# CADDX.net
KiCad netlist of a schematic drawn in Altium Designer
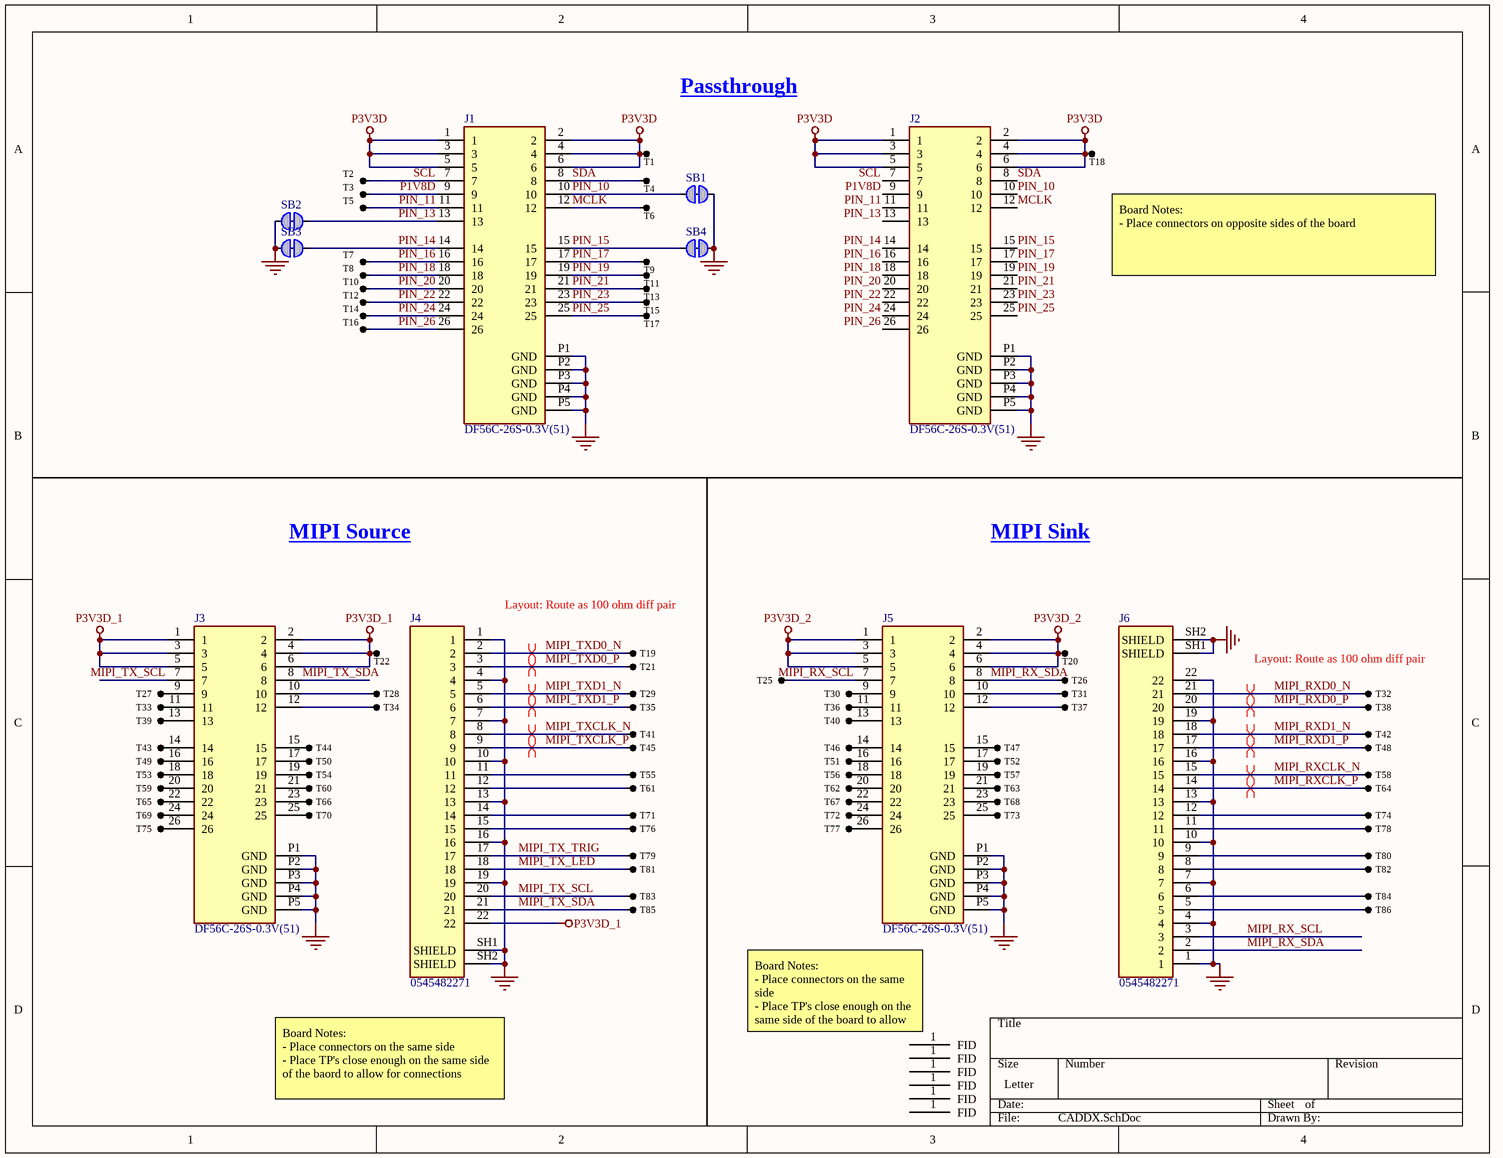
[diagram p0: CADDX.SchDoc]

(export (version "E")
  (design (tool "Eeschema 10.0.6"))
  (components
    (comp (ref "FID1") (value "FID") (footprint "FID_040") (libsource (lib "AiC RVP Adapter") (part "FID")))
    (comp (ref "FID2") (value "FID") (footprint "FID_040") (libsource (lib "AiC RVP Adapter") (part "FID")))
    (comp (ref "FID3") (value "FID") (footprint "FID_040") (libsource (lib "AiC RVP Adapter") (part "FID")))
    (comp (ref "FID4") (value "FID") (footprint "FID_040") (libsource (lib "AiC RVP Adapter") (part "FID")))
    (comp (ref "FID5") (value "FID") (footprint "FID_040") (libsource (lib "AiC RVP Adapter") (part "FID")))
    (comp (ref "FID6") (value "FID") (footprint "FID_040") (libsource (lib "AiC RVP Adapter") (part "FID")))
    (comp (ref "J1")
      (value "DF56C-26S-0.3V(51)")
      (footprint "HRS_DF56C-26S-0.3V(51)")
      (description "0.3mm Pitch, Vertical Mating, Board-to-Fine Coaxial Cable, -35 ℃ to 85 ℃, RoHS")
      (fields (field (name "MANUFACTURER") "Hirose"))
      (libsource (lib "CADDX_passthrough") (part "DF56C-26S-0.3V(51)"))
    )
    (comp (ref "J2")
      (value "DF56C-26S-0.3V(51)")
      (footprint "HRS_DF56C-26S-0.3V(51)")
      (description "0.3mm Pitch, Vertical Mating, Board-to-Fine Coaxial Cable, -35 ℃ to 85 ℃, RoHS")
      (fields (field (name "MANUFACTURER") "Hirose"))
      (libsource (lib "CADDX_passthrough") (part "DF56C-26S-0.3V(51)"))
    )
    (comp (ref "J3")
      (value "DF56C-26S-0.3V(51)")
      (footprint "HRS_DF56C-26S-0.3V(51)")
      (description "0.3mm Pitch, Vertical Mating, Board-to-Fine Coaxial Cable, -35 ℃ to 85 ℃, RoHS")
      (fields (field (name "MANUFACTURER") "Hirose"))
      (libsource (lib "CADDX_passthrough") (part "DF56C-26S-0.3V(51)"))
    )
    (comp (ref "J4")
      (value "0545482271")
      (footprint "MOLEX_54548-2271")
      (description "CONN FFC BOTTOM 22POS 0.50MM R/A")
      (fields (field (name "MANUFACTURER") "Molex"))
      (libsource (lib "") (part "54548-2271_1"))
    )
    (comp (ref "J5")
      (value "DF56C-26S-0.3V(51)")
      (footprint "HRS_DF56C-26S-0.3V(51)")
      (description "0.3mm Pitch, Vertical Mating, Board-to-Fine Coaxial Cable, -35 ℃ to 85 ℃, RoHS")
      (fields (field (name "MANUFACTURER") "Hirose"))
      (libsource (lib "CADDX_passthrough") (part "DF56C-26S-0.3V(51)"))
    )
    (comp (ref "J6")
      (value "0545482271")
      (footprint "MOLEX_54548-2271")
      (description "CONN FFC BOTTOM 22POS 0.50MM R/A")
      (fields (field (name "MANUFACTURER") "Molex"))
      (libsource (lib "CADDX_passthrough") (part "54548-2271"))
    )
    (comp (ref "SB1")
      (value "Solderbridge")
      (footprint "Solderbridge_Shorted")
      (description "Shorted Solderbridge")
      (fields
        (field (name "PART NUMBER") "Solderbridge Shorted")
        (field (name "PUBLISHER") "Nordic Semiconductor")
      )
      (libsource (lib "Tiger_Ti180") (part "Solderbridge Shorted"))
    )
    (comp (ref "SB2")
      (value "Solderbridge")
      (footprint "Solderbridge_Shorted")
      (description "Shorted Solderbridge")
      (fields
        (field (name "PART NUMBER") "Solderbridge Shorted")
        (field (name "PUBLISHER") "Nordic Semiconductor")
      )
      (libsource (lib "Tiger_Ti180") (part "Solderbridge Shorted"))
    )
    (comp (ref "SB3")
      (value "Solderbridge")
      (footprint "Solderbridge_Shorted")
      (description "Shorted Solderbridge")
      (fields
        (field (name "PART NUMBER") "Solderbridge Shorted")
        (field (name "PUBLISHER") "Nordic Semiconductor")
      )
      (libsource (lib "Tiger_Ti180") (part "Solderbridge Shorted"))
    )
    (comp (ref "SB4")
      (value "Solderbridge")
      (footprint "Solderbridge_Shorted")
      (description "Shorted Solderbridge")
      (fields
        (field (name "PART NUMBER") "Solderbridge Shorted")
        (field (name "PUBLISHER") "Nordic Semiconductor")
      )
      (libsource (lib "Tiger_Ti180") (part "Solderbridge Shorted"))
    )
    (comp (ref "T1")
      (value "~")
      (footprint "TP 1mm")
      (description "test point")
      (libsource (lib "Tiger_Ti180") (part "TP_S"))
    )
    (comp (ref "T2")
      (value "~")
      (footprint "TP 1mm")
      (description "test point")
      (libsource (lib "Tiger_Ti180") (part "TP_S"))
    )
    (comp (ref "T3")
      (value "~")
      (footprint "TP 1mm")
      (description "test point")
      (libsource (lib "Tiger_Ti180") (part "TP_S"))
    )
    (comp (ref "T4")
      (value "~")
      (footprint "TP 1mm")
      (description "test point")
      (libsource (lib "Tiger_Ti180") (part "TP_S"))
    )
    (comp (ref "T5")
      (value "~")
      (footprint "TP 1mm")
      (description "test point")
      (libsource (lib "Tiger_Ti180") (part "TP_S"))
    )
    (comp (ref "T6")
      (value "~")
      (footprint "TP 1mm")
      (description "test point")
      (libsource (lib "Tiger_Ti180") (part "TP_S"))
    )
    (comp (ref "T7")
      (value "~")
      (footprint "TP 1mm")
      (description "test point")
      (libsource (lib "Tiger_Ti180") (part "TP_S"))
    )
    (comp (ref "T8")
      (value "~")
      (footprint "TP 1mm")
      (description "test point")
      (libsource (lib "Tiger_Ti180") (part "TP_S"))
    )
    (comp (ref "T9")
      (value "~")
      (footprint "TP 1mm")
      (description "test point")
      (libsource (lib "Tiger_Ti180") (part "TP_S"))
    )
    (comp (ref "T10")
      (value "~")
      (footprint "TP 1mm")
      (description "test point")
      (libsource (lib "Tiger_Ti180") (part "TP_S"))
    )
    (comp (ref "T11")
      (value "~")
      (footprint "TP 1mm")
      (description "test point")
      (libsource (lib "Tiger_Ti180") (part "TP_S"))
    )
    (comp (ref "T12")
      (value "~")
      (footprint "TP 1mm")
      (description "test point")
      (libsource (lib "Tiger_Ti180") (part "TP_S"))
    )
    (comp (ref "T13")
      (value "~")
      (footprint "TP 1mm")
      (description "test point")
      (libsource (lib "Tiger_Ti180") (part "TP_S"))
    )
    (comp (ref "T14")
      (value "~")
      (footprint "TP 1mm")
      (description "test point")
      (libsource (lib "Tiger_Ti180") (part "TP_S"))
    )
    (comp (ref "T15")
      (value "~")
      (footprint "TP 1mm")
      (description "test point")
      (libsource (lib "Tiger_Ti180") (part "TP_S"))
    )
    (comp (ref "T16")
      (value "~")
      (footprint "TP 1mm")
      (description "test point")
      (libsource (lib "Tiger_Ti180") (part "TP_S"))
    )
    (comp (ref "T17")
      (value "~")
      (footprint "TP 1mm")
      (description "test point")
      (libsource (lib "Tiger_Ti180") (part "TP_S"))
    )
    (comp (ref "T18")
      (value "~")
      (footprint "TP 1mm")
      (description "test point")
      (libsource (lib "Tiger_Ti180") (part "TP_S"))
    )
    (comp (ref "T19")
      (value "~")
      (footprint "TP 1mm")
      (description "test point")
      (libsource (lib "Tiger_Ti180") (part "TP_S"))
    )
    (comp (ref "T20")
      (value "~")
      (footprint "TP 1mm")
      (description "test point")
      (libsource (lib "Tiger_Ti180") (part "TP_S"))
    )
    (comp (ref "T21")
      (value "~")
      (footprint "TP 1mm")
      (description "test point")
      (libsource (lib "Tiger_Ti180") (part "TP_S"))
    )
    (comp (ref "T22")
      (value "~")
      (footprint "TP 1mm")
      (description "test point")
      (libsource (lib "Tiger_Ti180") (part "TP_S"))
    )
    (comp (ref "T25")
      (value "~")
      (footprint "TP 1mm")
      (description "test point")
      (libsource (lib "Tiger_Ti180") (part "TP_S"))
    )
    (comp (ref "T26")
      (value "~")
      (footprint "TP 1mm")
      (description "test point")
      (libsource (lib "Tiger_Ti180") (part "TP_S"))
    )
    (comp (ref "T27")
      (value "~")
      (footprint "TP 1mm")
      (description "test point")
      (libsource (lib "Tiger_Ti180") (part "TP_S"))
    )
    (comp (ref "T28")
      (value "~")
      (footprint "TP 1mm")
      (description "test point")
      (libsource (lib "Tiger_Ti180") (part "TP_S"))
    )
    (comp (ref "T29")
      (value "~")
      (footprint "TP 1mm")
      (description "test point")
      (libsource (lib "Tiger_Ti180") (part "TP_S"))
    )
    (comp (ref "T30")
      (value "~")
      (footprint "TP 1mm")
      (description "test point")
      (libsource (lib "Tiger_Ti180") (part "TP_S"))
    )
    (comp (ref "T31")
      (value "~")
      (footprint "TP 1mm")
      (description "test point")
      (libsource (lib "Tiger_Ti180") (part "TP_S"))
    )
    (comp (ref "T32")
      (value "~")
      (footprint "TP 1mm")
      (description "test point")
      (libsource (lib "Tiger_Ti180") (part "TP_S"))
    )
    (comp (ref "T33")
      (value "~")
      (footprint "TP 1mm")
      (description "test point")
      (libsource (lib "Tiger_Ti180") (part "TP_S"))
    )
    (comp (ref "T34")
      (value "~")
      (footprint "TP 1mm")
      (description "test point")
      (libsource (lib "Tiger_Ti180") (part "TP_S"))
    )
    (comp (ref "T35")
      (value "~")
      (footprint "TP 1mm")
      (description "test point")
      (libsource (lib "Tiger_Ti180") (part "TP_S"))
    )
    (comp (ref "T36")
      (value "~")
      (footprint "TP 1mm")
      (description "test point")
      (libsource (lib "Tiger_Ti180") (part "TP_S"))
    )
    (comp (ref "T37")
      (value "~")
      (footprint "TP 1mm")
      (description "test point")
      (libsource (lib "Tiger_Ti180") (part "TP_S"))
    )
    (comp (ref "T38")
      (value "~")
      (footprint "TP 1mm")
      (description "test point")
      (libsource (lib "Tiger_Ti180") (part "TP_S"))
    )
    (comp (ref "T39")
      (value "~")
      (footprint "TP 1mm")
      (description "test point")
      (libsource (lib "Tiger_Ti180") (part "TP_S"))
    )
    (comp (ref "T40")
      (value "~")
      (footprint "TP 1mm")
      (description "test point")
      (libsource (lib "Tiger_Ti180") (part "TP_S"))
    )
    (comp (ref "T41")
      (value "~")
      (footprint "TP 1mm")
      (description "test point")
      (libsource (lib "Tiger_Ti180") (part "TP_S"))
    )
    (comp (ref "T42")
      (value "~")
      (footprint "TP 1mm")
      (description "test point")
      (libsource (lib "Tiger_Ti180") (part "TP_S"))
    )
    (comp (ref "T43")
      (value "~")
      (footprint "TP 1mm")
      (description "test point")
      (libsource (lib "Tiger_Ti180") (part "TP_S"))
    )
    (comp (ref "T44")
      (value "~")
      (footprint "TP 1mm")
      (description "test point")
      (libsource (lib "Tiger_Ti180") (part "TP_S"))
    )
    (comp (ref "T45")
      (value "~")
      (footprint "TP 1mm")
      (description "test point")
      (libsource (lib "Tiger_Ti180") (part "TP_S"))
    )
    (comp (ref "T46")
      (value "~")
      (footprint "TP 1mm")
      (description "test point")
      (libsource (lib "Tiger_Ti180") (part "TP_S"))
    )
    (comp (ref "T47")
      (value "~")
      (footprint "TP 1mm")
      (description "test point")
      (libsource (lib "Tiger_Ti180") (part "TP_S"))
    )
    (comp (ref "T48")
      (value "~")
      (footprint "TP 1mm")
      (description "test point")
      (libsource (lib "Tiger_Ti180") (part "TP_S"))
    )
    (comp (ref "T49")
      (value "~")
      (footprint "TP 1mm")
      (description "test point")
      (libsource (lib "Tiger_Ti180") (part "TP_S"))
    )
    (comp (ref "T50")
      (value "~")
      (footprint "TP 1mm")
      (description "test point")
      (libsource (lib "Tiger_Ti180") (part "TP_S"))
    )
    (comp (ref "T51")
      (value "~")
      (footprint "TP 1mm")
      (description "test point")
      (libsource (lib "Tiger_Ti180") (part "TP_S"))
    )
    (comp (ref "T52")
      (value "~")
      (footprint "TP 1mm")
      (description "test point")
      (libsource (lib "Tiger_Ti180") (part "TP_S"))
    )
    (comp (ref "T53")
      (value "~")
      (footprint "TP 1mm")
      (description "test point")
      (libsource (lib "Tiger_Ti180") (part "TP_S"))
    )
    (comp (ref "T54")
      (value "~")
      (footprint "TP 1mm")
      (description "test point")
      (libsource (lib "Tiger_Ti180") (part "TP_S"))
    )
    (comp (ref "T55")
      (value "~")
      (footprint "TP 1mm")
      (description "test point")
      (libsource (lib "Tiger_Ti180") (part "TP_S"))
    )
    (comp (ref "T56")
      (value "~")
      (footprint "TP 1mm")
      (description "test point")
      (libsource (lib "Tiger_Ti180") (part "TP_S"))
    )
    (comp (ref "T57")
      (value "~")
      (footprint "TP 1mm")
      (description "test point")
      (libsource (lib "Tiger_Ti180") (part "TP_S"))
    )
    (comp (ref "T58")
      (value "~")
      (footprint "TP 1mm")
      (description "test point")
      (libsource (lib "Tiger_Ti180") (part "TP_S"))
    )
    (comp (ref "T59")
      (value "~")
      (footprint "TP 1mm")
      (description "test point")
      (libsource (lib "Tiger_Ti180") (part "TP_S"))
    )
    (comp (ref "T60")
      (value "~")
      (footprint "TP 1mm")
      (description "test point")
      (libsource (lib "Tiger_Ti180") (part "TP_S"))
    )
    (comp (ref "T61")
      (value "~")
      (footprint "TP 1mm")
      (description "test point")
      (libsource (lib "Tiger_Ti180") (part "TP_S"))
    )
    (comp (ref "T62")
      (value "~")
      (footprint "TP 1mm")
      (description "test point")
      (libsource (lib "Tiger_Ti180") (part "TP_S"))
    )
    (comp (ref "T63")
      (value "~")
      (footprint "TP 1mm")
      (description "test point")
      (libsource (lib "Tiger_Ti180") (part "TP_S"))
    )
    (comp (ref "T64")
      (value "~")
      (footprint "TP 1mm")
      (description "test point")
      (libsource (lib "Tiger_Ti180") (part "TP_S"))
    )
    (comp (ref "T65")
      (value "~")
      (footprint "TP 1mm")
      (description "test point")
      (libsource (lib "Tiger_Ti180") (part "TP_S"))
    )
    (comp (ref "T66")
      (value "~")
      (footprint "TP 1mm")
      (description "test point")
      (libsource (lib "Tiger_Ti180") (part "TP_S"))
    )
    (comp (ref "T67")
      (value "~")
      (footprint "TP 1mm")
      (description "test point")
      (libsource (lib "Tiger_Ti180") (part "TP_S"))
    )
    (comp (ref "T68")
      (value "~")
      (footprint "TP 1mm")
      (description "test point")
      (libsource (lib "Tiger_Ti180") (part "TP_S"))
    )
    (comp (ref "T69")
      (value "~")
      (footprint "TP 1mm")
      (description "test point")
      (libsource (lib "Tiger_Ti180") (part "TP_S"))
    )
    (comp (ref "T70")
      (value "~")
      (footprint "TP 1mm")
      (description "test point")
      (libsource (lib "Tiger_Ti180") (part "TP_S"))
    )
    (comp (ref "T71")
      (value "~")
      (footprint "TP 1mm")
      (description "test point")
      (libsource (lib "Tiger_Ti180") (part "TP_S"))
    )
    (comp (ref "T72")
      (value "~")
      (footprint "TP 1mm")
      (description "test point")
      (libsource (lib "Tiger_Ti180") (part "TP_S"))
    )
    (comp (ref "T73")
      (value "~")
      (footprint "TP 1mm")
      (description "test point")
      (libsource (lib "Tiger_Ti180") (part "TP_S"))
    )
    (comp (ref "T74")
      (value "~")
      (footprint "TP 1mm")
      (description "test point")
      (libsource (lib "Tiger_Ti180") (part "TP_S"))
    )
    (comp (ref "T75")
      (value "~")
      (footprint "TP 1mm")
      (description "test point")
      (libsource (lib "Tiger_Ti180") (part "TP_S"))
    )
    (comp (ref "T76")
      (value "~")
      (footprint "TP 1mm")
      (description "test point")
      (libsource (lib "Tiger_Ti180") (part "TP_S"))
    )
    (comp (ref "T77")
      (value "~")
      (footprint "TP 1mm")
      (description "test point")
      (libsource (lib "Tiger_Ti180") (part "TP_S"))
    )
    (comp (ref "T78")
      (value "~")
      (footprint "TP 1mm")
      (description "test point")
      (libsource (lib "Tiger_Ti180") (part "TP_S"))
    )
    (comp (ref "T79")
      (value "~")
      (footprint "TP 1mm")
      (description "test point")
      (libsource (lib "Tiger_Ti180") (part "TP_S"))
    )
    (comp (ref "T80")
      (value "~")
      (footprint "TP 1mm")
      (description "test point")
      (libsource (lib "Tiger_Ti180") (part "TP_S"))
    )
    (comp (ref "T81")
      (value "~")
      (footprint "TP 1mm")
      (description "test point")
      (libsource (lib "Tiger_Ti180") (part "TP_S"))
    )
    (comp (ref "T82")
      (value "~")
      (footprint "TP 1mm")
      (description "test point")
      (libsource (lib "Tiger_Ti180") (part "TP_S"))
    )
    (comp (ref "T83")
      (value "~")
      (footprint "TP 1mm")
      (description "test point")
      (libsource (lib "Tiger_Ti180") (part "TP_S"))
    )
    (comp (ref "T84")
      (value "~")
      (footprint "TP 1mm")
      (description "test point")
      (libsource (lib "Tiger_Ti180") (part "TP_S"))
    )
    (comp (ref "T85")
      (value "~")
      (footprint "TP 1mm")
      (description "test point")
      (libsource (lib "Tiger_Ti180") (part "TP_S"))
    )
    (comp (ref "T86")
      (value "~")
      (footprint "TP 1mm")
      (description "test point")
      (libsource (lib "Tiger_Ti180") (part "TP_S"))
    )
  )
  (nets
    (net (code "1") (name "/MCLK") (class "Default")
      (node (ref "J1") (pin "12") (pinfunction "12_12") (pintype "passive"))
      (node (ref "J2") (pin "12") (pinfunction "12_12") (pintype "passive"))
      (node (ref "T6") (pin "1") (pintype "passive"))
    )
    (net (code "2") (name "/MIPI_RXCLK_N") (class "Default")
      (node (ref "J6") (pin "15") (pinfunction "15_15") (pintype "passive"))
      (node (ref "T58") (pin "1") (pintype "passive"))
    )
    (net (code "3") (name "/MIPI_RXCLK_P") (class "Default")
      (node (ref "J6") (pin "14") (pinfunction "14_14") (pintype "passive"))
      (node (ref "T64") (pin "1") (pintype "passive"))
    )
    (net (code "4") (name "/MIPI_RXD0_N") (class "Default")
      (node (ref "J6") (pin "21") (pinfunction "21_21") (pintype "passive"))
      (node (ref "T32") (pin "1") (pintype "passive"))
    )
    (net (code "5") (name "/MIPI_RXD0_P") (class "Default")
      (node (ref "J6") (pin "20") (pinfunction "20_20") (pintype "passive"))
      (node (ref "T38") (pin "1") (pintype "passive"))
    )
    (net (code "6") (name "/MIPI_RXD1_N") (class "Default")
      (node (ref "J6") (pin "18") (pinfunction "18_18") (pintype "passive"))
      (node (ref "T42") (pin "1") (pintype "passive"))
    )
    (net (code "7") (name "/MIPI_RXD1_P") (class "Default")
      (node (ref "J6") (pin "17") (pinfunction "17_17") (pintype "passive"))
      (node (ref "T48") (pin "1") (pintype "passive"))
    )
    (net (code "8") (name "/MIPI_RX_SCL") (class "Default")
      (node (ref "J5") (pin "7") (pinfunction "7_7") (pintype "passive"))
      (node (ref "J6") (pin "3") (pinfunction "3_3") (pintype "passive"))
      (node (ref "T25") (pin "1") (pintype "passive"))
    )
    (net (code "9") (name "/MIPI_RX_SDA") (class "Default")
      (node (ref "J5") (pin "8") (pinfunction "8_8") (pintype "passive"))
      (node (ref "J6") (pin "2") (pinfunction "2_2") (pintype "passive"))
      (node (ref "T26") (pin "1") (pintype "passive"))
    )
    (net (code "10") (name "/MIPI_TXCLK_N") (class "Default")
      (node (ref "J4") (pin "8") (pinfunction "8_8") (pintype "passive"))
      (node (ref "T41") (pin "1") (pintype "passive"))
    )
    (net (code "11") (name "/MIPI_TXCLK_P") (class "Default")
      (node (ref "J4") (pin "9") (pinfunction "9_9") (pintype "passive"))
      (node (ref "T45") (pin "1") (pintype "passive"))
    )
    (net (code "12") (name "/MIPI_TXD0_N") (class "Default")
      (node (ref "J4") (pin "2") (pinfunction "2_2") (pintype "passive"))
      (node (ref "T19") (pin "1") (pintype "passive"))
    )
    (net (code "13") (name "/MIPI_TXD0_P") (class "Default")
      (node (ref "J4") (pin "3") (pinfunction "3_3") (pintype "passive"))
      (node (ref "T21") (pin "1") (pintype "passive"))
    )
    (net (code "14") (name "/MIPI_TXD1_N") (class "Default")
      (node (ref "J4") (pin "5") (pinfunction "5_5") (pintype "passive"))
      (node (ref "T29") (pin "1") (pintype "passive"))
    )
    (net (code "15") (name "/MIPI_TXD1_P") (class "Default")
      (node (ref "J4") (pin "6") (pinfunction "6_6") (pintype "passive"))
      (node (ref "T35") (pin "1") (pintype "passive"))
    )
    (net (code "16") (name "/MIPI_TX_LED") (class "Default")
      (node (ref "J4") (pin "18") (pinfunction "18_18") (pintype "passive"))
      (node (ref "T81") (pin "1") (pintype "passive"))
    )
    (net (code "17") (name "/MIPI_TX_SCL") (class "Default")
      (node (ref "J3") (pin "7") (pinfunction "7_7") (pintype "passive"))
      (node (ref "J4") (pin "20") (pinfunction "20_20") (pintype "passive"))
      (node (ref "T83") (pin "1") (pintype "passive"))
    )
    (net (code "18") (name "/MIPI_TX_SDA") (class "Default")
      (node (ref "J3") (pin "8") (pinfunction "8_8") (pintype "passive"))
      (node (ref "J4") (pin "21") (pinfunction "21_21") (pintype "passive"))
      (node (ref "T85") (pin "1") (pintype "passive"))
    )
    (net (code "19") (name "/MIPI_TX_TRIG") (class "Default")
      (node (ref "J4") (pin "17") (pinfunction "17_17") (pintype "passive"))
      (node (ref "T79") (pin "1") (pintype "passive"))
    )
    (net (code "20") (name "/P1V8D") (class "Default")
      (node (ref "J1") (pin "9") (pinfunction "9_9") (pintype "passive"))
      (node (ref "J2") (pin "9") (pinfunction "9_9") (pintype "passive"))
      (node (ref "T3") (pin "1") (pintype "passive"))
    )
    (net (code "21") (name "/PIN_10") (class "Default")
      (node (ref "J1") (pin "10") (pinfunction "10_10") (pintype "passive"))
      (node (ref "J2") (pin "10") (pinfunction "10_10") (pintype "passive"))
      (node (ref "SB1") (pin "2") (pinfunction "1_2") (pintype "passive"))
    )
    (net (code "22") (name "/PIN_11") (class "Default")
      (node (ref "J1") (pin "11") (pinfunction "11_11") (pintype "passive"))
      (node (ref "J2") (pin "11") (pinfunction "11_11") (pintype "passive"))
      (node (ref "T5") (pin "1") (pintype "passive"))
    )
    (net (code "23") (name "/PIN_13") (class "Default")
      (node (ref "J1") (pin "13") (pinfunction "13_13") (pintype "passive"))
      (node (ref "J2") (pin "13") (pinfunction "13_13") (pintype "passive"))
      (node (ref "SB2") (pin "1") (pinfunction "0_1") (pintype "passive"))
    )
    (net (code "24") (name "/PIN_14") (class "Default")
      (node (ref "J1") (pin "14") (pinfunction "14_14") (pintype "passive"))
      (node (ref "J2") (pin "14") (pinfunction "14_14") (pintype "passive"))
      (node (ref "SB3") (pin "1") (pinfunction "0_1") (pintype "passive"))
    )
    (net (code "25") (name "/PIN_15") (class "Default")
      (node (ref "J1") (pin "15") (pinfunction "15_15") (pintype "passive"))
      (node (ref "J2") (pin "15") (pinfunction "15_15") (pintype "passive"))
      (node (ref "SB4") (pin "2") (pinfunction "1_2") (pintype "passive"))
    )
    (net (code "26") (name "/PIN_16") (class "Default")
      (node (ref "J1") (pin "16") (pinfunction "16_16") (pintype "passive"))
      (node (ref "J2") (pin "16") (pinfunction "16_16") (pintype "passive"))
      (node (ref "T7") (pin "1") (pintype "passive"))
    )
    (net (code "27") (name "/PIN_17") (class "Default")
      (node (ref "J1") (pin "17") (pinfunction "17_17") (pintype "passive"))
      (node (ref "J2") (pin "17") (pinfunction "17_17") (pintype "passive"))
      (node (ref "T9") (pin "1") (pintype "passive"))
    )
    (net (code "28") (name "/PIN_18") (class "Default")
      (node (ref "J1") (pin "18") (pinfunction "18_18") (pintype "passive"))
      (node (ref "J2") (pin "18") (pinfunction "18_18") (pintype "passive"))
      (node (ref "T8") (pin "1") (pintype "passive"))
    )
    (net (code "29") (name "/PIN_19") (class "Default")
      (node (ref "J1") (pin "19") (pinfunction "19_19") (pintype "passive"))
      (node (ref "J2") (pin "19") (pinfunction "19_19") (pintype "passive"))
      (node (ref "T11") (pin "1") (pintype "passive"))
    )
    (net (code "30") (name "/PIN_20") (class "Default")
      (node (ref "J1") (pin "20") (pinfunction "20_20") (pintype "passive"))
      (node (ref "J2") (pin "20") (pinfunction "20_20") (pintype "passive"))
      (node (ref "T10") (pin "1") (pintype "passive"))
    )
    (net (code "31") (name "/PIN_21") (class "Default")
      (node (ref "J1") (pin "21") (pinfunction "21_21") (pintype "passive"))
      (node (ref "J2") (pin "21") (pinfunction "21_21") (pintype "passive"))
      (node (ref "T13") (pin "1") (pintype "passive"))
    )
    (net (code "32") (name "/PIN_22") (class "Default")
      (node (ref "J1") (pin "22") (pinfunction "22_22") (pintype "passive"))
      (node (ref "J2") (pin "22") (pinfunction "22_22") (pintype "passive"))
      (node (ref "T12") (pin "1") (pintype "passive"))
    )
    (net (code "33") (name "/PIN_23") (class "Default")
      (node (ref "J1") (pin "23") (pinfunction "23_23") (pintype "passive"))
      (node (ref "J2") (pin "23") (pinfunction "23_23") (pintype "passive"))
      (node (ref "T15") (pin "1") (pintype "passive"))
    )
    (net (code "34") (name "/PIN_24") (class "Default")
      (node (ref "J1") (pin "24") (pinfunction "24_24") (pintype "passive"))
      (node (ref "J2") (pin "24") (pinfunction "24_24") (pintype "passive"))
      (node (ref "T14") (pin "1") (pintype "passive"))
    )
    (net (code "35") (name "/PIN_25") (class "Default")
      (node (ref "J1") (pin "25") (pinfunction "25_25") (pintype "passive"))
      (node (ref "J2") (pin "25") (pinfunction "25_25") (pintype "passive"))
      (node (ref "T17") (pin "1") (pintype "passive"))
    )
    (net (code "36") (name "/PIN_26") (class "Default")
      (node (ref "J1") (pin "26") (pinfunction "26_26") (pintype "passive"))
      (node (ref "J2") (pin "26") (pinfunction "26_26") (pintype "passive"))
      (node (ref "T16") (pin "1") (pintype "passive"))
    )
    (net (code "37") (name "/SCL") (class "Default")
      (node (ref "J1") (pin "7") (pinfunction "7_7") (pintype "passive"))
      (node (ref "J2") (pin "7") (pinfunction "7_7") (pintype "passive"))
      (node (ref "T2") (pin "1") (pintype "passive"))
    )
    (net (code "38") (name "/SDA") (class "Default")
      (node (ref "J1") (pin "8") (pinfunction "8_8") (pintype "passive"))
      (node (ref "J2") (pin "8") (pinfunction "8_8") (pintype "passive"))
      (node (ref "T4") (pin "1") (pintype "passive"))
    )
    (net (code "39") (name "GND") (class "Default")
      (node (ref "J1") (pin "P1") (pinfunction "GND_P1") (pintype "power_in"))
      (node (ref "J1") (pin "P2") (pinfunction "GND_P2") (pintype "power_in"))
      (node (ref "J1") (pin "P3") (pinfunction "GND_P3") (pintype "power_in"))
      (node (ref "J1") (pin "P4") (pinfunction "GND_P4") (pintype "power_in"))
      (node (ref "J1") (pin "P5") (pinfunction "GND_P5") (pintype "power_in"))
      (node (ref "J2") (pin "P1") (pinfunction "GND_P1") (pintype "power_in"))
      (node (ref "J2") (pin "P2") (pinfunction "GND_P2") (pintype "power_in"))
      (node (ref "J2") (pin "P3") (pinfunction "GND_P3") (pintype "power_in"))
      (node (ref "J2") (pin "P4") (pinfunction "GND_P4") (pintype "power_in"))
      (node (ref "J2") (pin "P5") (pinfunction "GND_P5") (pintype "power_in"))
      (node (ref "J3") (pin "P1") (pinfunction "GND_P1") (pintype "power_in"))
      (node (ref "J3") (pin "P2") (pinfunction "GND_P2") (pintype "power_in"))
      (node (ref "J3") (pin "P3") (pinfunction "GND_P3") (pintype "power_in"))
      (node (ref "J3") (pin "P4") (pinfunction "GND_P4") (pintype "power_in"))
      (node (ref "J3") (pin "P5") (pinfunction "GND_P5") (pintype "power_in"))
      (node (ref "J4") (pin "1") (pinfunction "1_1") (pintype "passive"))
      (node (ref "J4") (pin "10") (pinfunction "10_10") (pintype "passive"))
      (node (ref "J4") (pin "13") (pinfunction "13_13") (pintype "passive"))
      (node (ref "J4") (pin "16") (pinfunction "16_16") (pintype "passive"))
      (node (ref "J4") (pin "19") (pinfunction "19_19") (pintype "passive"))
      (node (ref "J4") (pin "4") (pinfunction "4_4") (pintype "passive"))
      (node (ref "J4") (pin "7") (pinfunction "7_7") (pintype "passive"))
      (node (ref "J4") (pin "SH1") (pinfunction "SHIELD_SH1") (pintype "passive"))
      (node (ref "J4") (pin "SH2") (pinfunction "SHIELD_SH2") (pintype "passive"))
      (node (ref "J5") (pin "P1") (pinfunction "GND_P1") (pintype "power_in"))
      (node (ref "J5") (pin "P2") (pinfunction "GND_P2") (pintype "power_in"))
      (node (ref "J5") (pin "P3") (pinfunction "GND_P3") (pintype "power_in"))
      (node (ref "J5") (pin "P4") (pinfunction "GND_P4") (pintype "power_in"))
      (node (ref "J5") (pin "P5") (pinfunction "GND_P5") (pintype "power_in"))
      (node (ref "J6") (pin "1") (pinfunction "1_1") (pintype "passive"))
      (node (ref "J6") (pin "10") (pinfunction "10_10") (pintype "passive"))
      (node (ref "J6") (pin "13") (pinfunction "13_13") (pintype "passive"))
      (node (ref "J6") (pin "16") (pinfunction "16_16") (pintype "passive"))
      (node (ref "J6") (pin "19") (pinfunction "19_19") (pintype "passive"))
      (node (ref "J6") (pin "22") (pinfunction "22_22") (pintype "passive"))
      (node (ref "J6") (pin "4") (pinfunction "4_4") (pintype "passive"))
      (node (ref "J6") (pin "7") (pinfunction "7_7") (pintype "passive"))
      (node (ref "J6") (pin "SH1") (pinfunction "SHIELD_SH1") (pintype "passive"))
      (node (ref "J6") (pin "SH2") (pinfunction "SHIELD_SH2") (pintype "passive"))
      (node (ref "SB1") (pin "1") (pinfunction "0_1") (pintype "passive"))
      (node (ref "SB2") (pin "2") (pinfunction "1_2") (pintype "passive"))
      (node (ref "SB3") (pin "2") (pinfunction "1_2") (pintype "passive"))
      (node (ref "SB4") (pin "1") (pinfunction "0_1") (pintype "passive"))
    )
    (net (code "40") (name "Net-(J3-Pad9)") (class "Default")
      (node (ref "J3") (pin "9") (pinfunction "9_9") (pintype "passive"))
      (node (ref "T27") (pin "1") (pintype "passive"))
    )
    (net (code "41") (name "Net-(J3-Pad10)") (class "Default")
      (node (ref "J3") (pin "10") (pinfunction "10_10") (pintype "passive"))
      (node (ref "T28") (pin "1") (pintype "passive"))
    )
    (net (code "42") (name "Net-(J3-Pad11)") (class "Default")
      (node (ref "J3") (pin "11") (pinfunction "11_11") (pintype "passive"))
      (node (ref "T33") (pin "1") (pintype "passive"))
    )
    (net (code "43") (name "Net-(J3-Pad12)") (class "Default")
      (node (ref "J3") (pin "12") (pinfunction "12_12") (pintype "passive"))
      (node (ref "T34") (pin "1") (pintype "passive"))
    )
    (net (code "44") (name "Net-(J3-Pad13)") (class "Default")
      (node (ref "J3") (pin "13") (pinfunction "13_13") (pintype "passive"))
      (node (ref "T39") (pin "1") (pintype "passive"))
    )
    (net (code "45") (name "Net-(J3-Pad14)") (class "Default")
      (node (ref "J3") (pin "14") (pinfunction "14_14") (pintype "passive"))
      (node (ref "T43") (pin "1") (pintype "passive"))
    )
    (net (code "46") (name "Net-(J3-Pad15)") (class "Default")
      (node (ref "J3") (pin "15") (pinfunction "15_15") (pintype "passive"))
      (node (ref "T44") (pin "1") (pintype "passive"))
    )
    (net (code "47") (name "Net-(J3-Pad16)") (class "Default")
      (node (ref "J3") (pin "16") (pinfunction "16_16") (pintype "passive"))
      (node (ref "T49") (pin "1") (pintype "passive"))
    )
    (net (code "48") (name "Net-(J3-Pad17)") (class "Default")
      (node (ref "J3") (pin "17") (pinfunction "17_17") (pintype "passive"))
      (node (ref "T50") (pin "1") (pintype "passive"))
    )
    (net (code "49") (name "Net-(J3-Pad18)") (class "Default")
      (node (ref "J3") (pin "18") (pinfunction "18_18") (pintype "passive"))
      (node (ref "T53") (pin "1") (pintype "passive"))
    )
    (net (code "50") (name "Net-(J3-Pad19)") (class "Default")
      (node (ref "J3") (pin "19") (pinfunction "19_19") (pintype "passive"))
      (node (ref "T54") (pin "1") (pintype "passive"))
    )
    (net (code "51") (name "Net-(J3-Pad20)") (class "Default")
      (node (ref "J3") (pin "20") (pinfunction "20_20") (pintype "passive"))
      (node (ref "T59") (pin "1") (pintype "passive"))
    )
    (net (code "52") (name "Net-(J3-Pad21)") (class "Default")
      (node (ref "J3") (pin "21") (pinfunction "21_21") (pintype "passive"))
      (node (ref "T60") (pin "1") (pintype "passive"))
    )
    (net (code "53") (name "Net-(J3-Pad22)") (class "Default")
      (node (ref "J3") (pin "22") (pinfunction "22_22") (pintype "passive"))
      (node (ref "T65") (pin "1") (pintype "passive"))
    )
    (net (code "54") (name "Net-(J3-Pad23)") (class "Default")
      (node (ref "J3") (pin "23") (pinfunction "23_23") (pintype "passive"))
      (node (ref "T66") (pin "1") (pintype "passive"))
    )
    (net (code "55") (name "Net-(J3-Pad24)") (class "Default")
      (node (ref "J3") (pin "24") (pinfunction "24_24") (pintype "passive"))
      (node (ref "T69") (pin "1") (pintype "passive"))
    )
    (net (code "56") (name "Net-(J3-Pad25)") (class "Default")
      (node (ref "J3") (pin "25") (pinfunction "25_25") (pintype "passive"))
      (node (ref "T70") (pin "1") (pintype "passive"))
    )
    (net (code "57") (name "Net-(J3-Pad26)") (class "Default")
      (node (ref "J3") (pin "26") (pinfunction "26_26") (pintype "passive"))
      (node (ref "T75") (pin "1") (pintype "passive"))
    )
    (net (code "58") (name "Net-(J4-Pad11)") (class "Default")
      (node (ref "J4") (pin "11") (pinfunction "11_11") (pintype "passive"))
      (node (ref "T55") (pin "1") (pintype "passive"))
    )
    (net (code "59") (name "Net-(J4-Pad12)") (class "Default")
      (node (ref "J4") (pin "12") (pinfunction "12_12") (pintype "passive"))
      (node (ref "T61") (pin "1") (pintype "passive"))
    )
    (net (code "60") (name "Net-(J4-Pad14)") (class "Default")
      (node (ref "J4") (pin "14") (pinfunction "14_14") (pintype "passive"))
      (node (ref "T71") (pin "1") (pintype "passive"))
    )
    (net (code "61") (name "Net-(J4-Pad15)") (class "Default")
      (node (ref "J4") (pin "15") (pinfunction "15_15") (pintype "passive"))
      (node (ref "T76") (pin "1") (pintype "passive"))
    )
    (net (code "62") (name "Net-(J5-Pad9)") (class "Default")
      (node (ref "J5") (pin "9") (pinfunction "9_9") (pintype "passive"))
      (node (ref "T30") (pin "1") (pintype "passive"))
    )
    (net (code "63") (name "Net-(J5-Pad10)") (class "Default")
      (node (ref "J5") (pin "10") (pinfunction "10_10") (pintype "passive"))
      (node (ref "T31") (pin "1") (pintype "passive"))
    )
    (net (code "64") (name "Net-(J5-Pad11)") (class "Default")
      (node (ref "J5") (pin "11") (pinfunction "11_11") (pintype "passive"))
      (node (ref "T36") (pin "1") (pintype "passive"))
    )
    (net (code "65") (name "Net-(J5-Pad12)") (class "Default")
      (node (ref "J5") (pin "12") (pinfunction "12_12") (pintype "passive"))
      (node (ref "T37") (pin "1") (pintype "passive"))
    )
    (net (code "66") (name "Net-(J5-Pad13)") (class "Default")
      (node (ref "J5") (pin "13") (pinfunction "13_13") (pintype "passive"))
      (node (ref "T40") (pin "1") (pintype "passive"))
    )
    (net (code "67") (name "Net-(J5-Pad14)") (class "Default")
      (node (ref "J5") (pin "14") (pinfunction "14_14") (pintype "passive"))
      (node (ref "T46") (pin "1") (pintype "passive"))
    )
    (net (code "68") (name "Net-(J5-Pad15)") (class "Default")
      (node (ref "J5") (pin "15") (pinfunction "15_15") (pintype "passive"))
      (node (ref "T47") (pin "1") (pintype "passive"))
    )
    (net (code "69") (name "Net-(J5-Pad16)") (class "Default")
      (node (ref "J5") (pin "16") (pinfunction "16_16") (pintype "passive"))
      (node (ref "T51") (pin "1") (pintype "passive"))
    )
    (net (code "70") (name "Net-(J5-Pad17)") (class "Default")
      (node (ref "J5") (pin "17") (pinfunction "17_17") (pintype "passive"))
      (node (ref "T52") (pin "1") (pintype "passive"))
    )
    (net (code "71") (name "Net-(J5-Pad18)") (class "Default")
      (node (ref "J5") (pin "18") (pinfunction "18_18") (pintype "passive"))
      (node (ref "T56") (pin "1") (pintype "passive"))
    )
    (net (code "72") (name "Net-(J5-Pad19)") (class "Default")
      (node (ref "J5") (pin "19") (pinfunction "19_19") (pintype "passive"))
      (node (ref "T57") (pin "1") (pintype "passive"))
    )
    (net (code "73") (name "Net-(J5-Pad20)") (class "Default")
      (node (ref "J5") (pin "20") (pinfunction "20_20") (pintype "passive"))
      (node (ref "T62") (pin "1") (pintype "passive"))
    )
    (net (code "74") (name "Net-(J5-Pad21)") (class "Default")
      (node (ref "J5") (pin "21") (pinfunction "21_21") (pintype "passive"))
      (node (ref "T63") (pin "1") (pintype "passive"))
    )
    (net (code "75") (name "Net-(J5-Pad22)") (class "Default")
      (node (ref "J5") (pin "22") (pinfunction "22_22") (pintype "passive"))
      (node (ref "T67") (pin "1") (pintype "passive"))
    )
    (net (code "76") (name "Net-(J5-Pad23)") (class "Default")
      (node (ref "J5") (pin "23") (pinfunction "23_23") (pintype "passive"))
      (node (ref "T68") (pin "1") (pintype "passive"))
    )
    (net (code "77") (name "Net-(J5-Pad24)") (class "Default")
      (node (ref "J5") (pin "24") (pinfunction "24_24") (pintype "passive"))
      (node (ref "T72") (pin "1") (pintype "passive"))
    )
    (net (code "78") (name "Net-(J5-Pad25)") (class "Default")
      (node (ref "J5") (pin "25") (pinfunction "25_25") (pintype "passive"))
      (node (ref "T73") (pin "1") (pintype "passive"))
    )
    (net (code "79") (name "Net-(J5-Pad26)") (class "Default")
      (node (ref "J5") (pin "26") (pinfunction "26_26") (pintype "passive"))
      (node (ref "T77") (pin "1") (pintype "passive"))
    )
    (net (code "80") (name "Net-(J6-Pad5)") (class "Default")
      (node (ref "J6") (pin "5") (pinfunction "5_5") (pintype "passive"))
      (node (ref "T86") (pin "1") (pintype "passive"))
    )
    (net (code "81") (name "Net-(J6-Pad6)") (class "Default")
      (node (ref "J6") (pin "6") (pinfunction "6_6") (pintype "passive"))
      (node (ref "T84") (pin "1") (pintype "passive"))
    )
    (net (code "82") (name "Net-(J6-Pad8)") (class "Default")
      (node (ref "J6") (pin "8") (pinfunction "8_8") (pintype "passive"))
      (node (ref "T82") (pin "1") (pintype "passive"))
    )
    (net (code "83") (name "Net-(J6-Pad9)") (class "Default")
      (node (ref "J6") (pin "9") (pinfunction "9_9") (pintype "passive"))
      (node (ref "T80") (pin "1") (pintype "passive"))
    )
    (net (code "84") (name "Net-(J6-Pad11)") (class "Default")
      (node (ref "J6") (pin "11") (pinfunction "11_11") (pintype "passive"))
      (node (ref "T78") (pin "1") (pintype "passive"))
    )
    (net (code "85") (name "Net-(J6-Pad12)") (class "Default")
      (node (ref "J6") (pin "12") (pinfunction "12_12") (pintype "passive"))
      (node (ref "T74") (pin "1") (pintype "passive"))
    )
    (net (code "86") (name "P3V3D") (class "Default")
      (node (ref "J1") (pin "1") (pinfunction "1_1") (pintype "passive"))
      (node (ref "J1") (pin "2") (pinfunction "2_2") (pintype "passive"))
      (node (ref "J1") (pin "3") (pinfunction "3_3") (pintype "passive"))
      (node (ref "J1") (pin "4") (pinfunction "4_4") (pintype "passive"))
      (node (ref "J1") (pin "5") (pinfunction "5_5") (pintype "passive"))
      (node (ref "J1") (pin "6") (pinfunction "6_6") (pintype "passive"))
      (node (ref "J2") (pin "1") (pinfunction "1_1") (pintype "passive"))
      (node (ref "J2") (pin "2") (pinfunction "2_2") (pintype "passive"))
      (node (ref "J2") (pin "3") (pinfunction "3_3") (pintype "passive"))
      (node (ref "J2") (pin "4") (pinfunction "4_4") (pintype "passive"))
      (node (ref "J2") (pin "5") (pinfunction "5_5") (pintype "passive"))
      (node (ref "J2") (pin "6") (pinfunction "6_6") (pintype "passive"))
      (node (ref "T1") (pin "1") (pintype "passive"))
      (node (ref "T18") (pin "1") (pintype "passive"))
    )
    (net (code "87") (name "P3V3D_1") (class "Default")
      (node (ref "J3") (pin "1") (pinfunction "1_1") (pintype "passive"))
      (node (ref "J3") (pin "2") (pinfunction "2_2") (pintype "passive"))
      (node (ref "J3") (pin "3") (pinfunction "3_3") (pintype "passive"))
      (node (ref "J3") (pin "4") (pinfunction "4_4") (pintype "passive"))
      (node (ref "J3") (pin "5") (pinfunction "5_5") (pintype "passive"))
      (node (ref "J3") (pin "6") (pinfunction "6_6") (pintype "passive"))
      (node (ref "J4") (pin "22") (pinfunction "22_22") (pintype "passive"))
      (node (ref "T22") (pin "1") (pintype "passive"))
    )
    (net (code "88") (name "P3V3D_2") (class "Default")
      (node (ref "J5") (pin "1") (pinfunction "1_1") (pintype "passive"))
      (node (ref "J5") (pin "2") (pinfunction "2_2") (pintype "passive"))
      (node (ref "J5") (pin "3") (pinfunction "3_3") (pintype "passive"))
      (node (ref "J5") (pin "4") (pinfunction "4_4") (pintype "passive"))
      (node (ref "J5") (pin "5") (pinfunction "5_5") (pintype "passive"))
      (node (ref "J5") (pin "6") (pinfunction "6_6") (pintype "passive"))
      (node (ref "T20") (pin "1") (pintype "passive"))
    )
    (net (code "89") (name "unconnected-(FID1-FID-Pad1)") (class "Default")
      (node (ref "FID1") (pin "1") (pinfunction "FID_1") (pintype "passive"))
    )
    (net (code "90") (name "unconnected-(FID2-FID-Pad1)") (class "Default")
      (node (ref "FID2") (pin "1") (pinfunction "FID_1") (pintype "passive"))
    )
    (net (code "91") (name "unconnected-(FID3-FID-Pad1)") (class "Default")
      (node (ref "FID3") (pin "1") (pinfunction "FID_1") (pintype "passive"))
    )
    (net (code "92") (name "unconnected-(FID4-FID-Pad1)") (class "Default")
      (node (ref "FID4") (pin "1") (pinfunction "FID_1") (pintype "passive"))
    )
    (net (code "93") (name "unconnected-(FID5-FID-Pad1)") (class "Default")
      (node (ref "FID5") (pin "1") (pinfunction "FID_1") (pintype "passive"))
    )
    (net (code "94") (name "unconnected-(FID6-FID-Pad1)") (class "Default")
      (node (ref "FID6") (pin "1") (pinfunction "FID_1") (pintype "passive"))
    )
  )
)
